# Clock_Sheet.net
KiCad netlist of a schematic drawn in Altium Designer
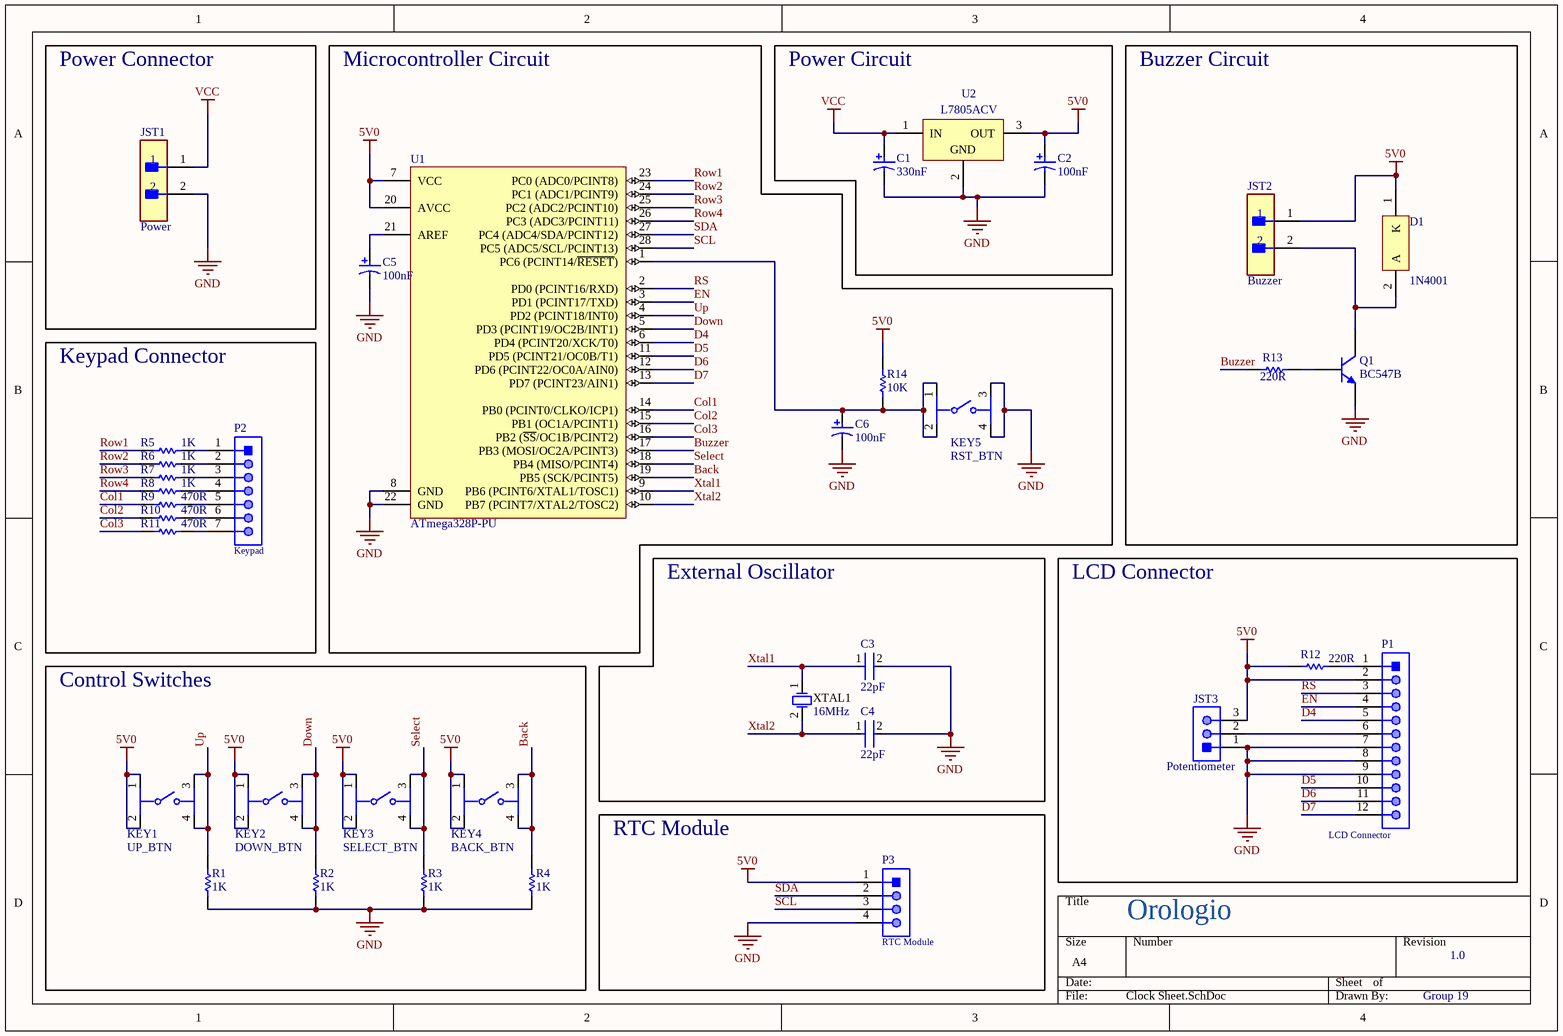
[diagram p0: Clock Sheet.SchDoc]

(export (version "E")
  (design (tool "Eeschema 10.0.6"))
  (components
    (comp (ref "C1")
      (value "330nF")
      (footprint "CAPPR65-350-1150X800X1250")
      (description "Aluminum Electrolytic Capacitor, 100 uF, +/- 20%, 50 V, -40 to 85 degC, 2-Pin THD, RoHS, Bulk")
      (fields (field (name "MANUFACTURER") "Panasonic") (field (name "VOLTAGE") "50V"))
      (libsource (lib "Altium Content Vault") (part "CAP-P-2"))
    )
    (comp (ref "C2")
      (value "100nF")
      (footprint "CAPPR65-350-1150X800X1250")
      (description "Aluminum Electrolytic Capacitor, 100 uF, +/- 20%, 50 V, -40 to 85 degC, 2-Pin THD, RoHS, Bulk")
      (fields (field (name "MANUFACTURER") "Panasonic") (field (name "VOLTAGE") "50V"))
      (libsource (lib "Altium Content Vault") (part "CAP-P-2"))
    )
    (comp (ref "C3")
      (value "22pF")
      (footprint "FP-RCE0K1-MFG")
      (description "Cap Ceramic 22pF 50V C0G ±5% Radial 5mm +125°C Automotive Bulk")
      (fields (field (name "TOLERANCE") "5%"))
      (libsource (lib "Altium Content Vault") (part "b4654b650e69147ec39a6b967a45e02"))
    )
    (comp (ref "C4")
      (value "22pF")
      (footprint "FP-RCE0K1-MFG")
      (description "Cap Ceramic 22pF 50V C0G ±5% Radial 5mm +125°C Automotive Bulk")
      (fields (field (name "TOLERANCE") "5%"))
      (libsource (lib "Altium Content Vault") (part "b4654b650e69147ec39a6b967a45e02"))
    )
    (comp (ref "C5")
      (value "100nF")
      (footprint "CAPPR65-350-1150X800X1250")
      (description "Aluminum Electrolytic Capacitor, 100 uF, +/- 20%, 50 V, -40 to 85 degC, 2-Pin THD, RoHS, Bulk")
      (fields (field (name "MANUFACTURER") "Panasonic") (field (name "VOLTAGE") "50V"))
      (libsource (lib "Altium Content Vault") (part "CAP-P-2"))
    )
    (comp (ref "C6")
      (value "100nF")
      (footprint "CAPPR65-350-1150X800X1250")
      (description "Aluminum Electrolytic Capacitor, 100 uF, +/- 20%, 50 V, -40 to 85 degC, 2-Pin THD, RoHS, Bulk")
      (fields (field (name "MANUFACTURER") "Panasonic") (field (name "VOLTAGE") "50V"))
      (libsource (lib "Altium Content Vault") (part "CAP-P-2"))
    )
    (comp (ref "D1")
      (value "1N4001")
      (footprint "ONSC-AXIAL_LEAD-2-59-10_P")
      (description "Standard Recovery Rectifier, 2-Pin Axial_Lead, Pb-Free, Bulk Bag")
      (fields (field (name "MANUFACTURER") "On Semiconductor"))
      (libsource (lib "Altium Content Vault") (part "ONSC-D-K1A2-2_A"))
    )
    (comp (ref "JST1")
      (value "Power")
      (footprint "FP-440054-2-MFG")
      (description "CONN HEADER VERT 2POS 2MM")
      (fields
        (field (name "MANUFACTURER") "TE Connectivity")
        (field (name "MANUFACTURER PART NUMBER") "440054-2")
      )
      (libsource (lib "Altium Content Vault") (part "3bc925449376181038e59eaffc5286c"))
    )
    (comp (ref "JST2")
      (value "Buzzer")
      (footprint "FP-440054-2-MFG")
      (description "CONN HEADER VERT 2POS 2MM")
      (fields
        (field (name "MANUFACTURER") "TE Connectivity")
        (field (name "MANUFACTURER PART NUMBER") "440054-2")
      )
      (libsource (lib "Altium Content Vault") (part "3bc925449376181038e59eaffc5286c"))
    )
    (comp (ref "JST3")
      (value "Potentiometer")
      (footprint "JST-B3B-PH-K-S-3_V")
      (fields (field (name "MANUFACTURER") "JST"))
      (libsource (lib "Altium Content Vault") (part "CN-1P-M-R3"))
    )
    (comp (ref "KEY1")
      (value "UP_BTN")
      (footprint "FP-1825910-2-0")
      (description "SWITCH TACTILE SPST-NO 0.05A 24V")
      (fields
        (field (name "OCTOPART") "https://octopart.com/1825910-2-te+connectivity-42270502")
        (field (name "MANUFACTURER") "TE")
      )
      (libsource (lib "Altium Content Vault") (part "b8895f3f4cefb76e1819d2863dba89b"))
    )
    (comp (ref "KEY2")
      (value "DOWN_BTN")
      (footprint "FP-1825910-2-0")
      (description "SWITCH TACTILE SPST-NO 0.05A 24V")
      (fields
        (field (name "OCTOPART") "https://octopart.com/1825910-2-te+connectivity-42270502")
        (field (name "MANUFACTURER") "TE")
      )
      (libsource (lib "Altium Content Vault") (part "b8895f3f4cefb76e1819d2863dba89b"))
    )
    (comp (ref "KEY3")
      (value "SELECT_BTN")
      (footprint "FP-1825910-2-0")
      (description "SWITCH TACTILE SPST-NO 0.05A 24V")
      (fields
        (field (name "OCTOPART") "https://octopart.com/1825910-2-te+connectivity-42270502")
        (field (name "MANUFACTURER") "TE")
      )
      (libsource (lib "Altium Content Vault") (part "b8895f3f4cefb76e1819d2863dba89b"))
    )
    (comp (ref "KEY4")
      (value "BACK_BTN")
      (footprint "FP-1825910-2-0")
      (description "SWITCH TACTILE SPST-NO 0.05A 24V")
      (fields
        (field (name "OCTOPART") "https://octopart.com/1825910-2-te+connectivity-42270502")
        (field (name "MANUFACTURER") "TE")
      )
      (libsource (lib "Altium Content Vault") (part "b8895f3f4cefb76e1819d2863dba89b"))
    )
    (comp (ref "KEY5")
      (value "RST_BTN")
      (footprint "FP-1825910-2-0")
      (description "SWITCH TACTILE SPST-NO 0.05A 24V")
      (fields
        (field (name "OCTOPART") "https://octopart.com/1825910-2-te+connectivity-42270502")
        (field (name "MANUFACTURER") "TE")
      )
      (libsource (lib "Altium Content Vault") (part "b8895f3f4cefb76e1819d2863dba89b"))
    )
    (comp (ref "P1")
      (value "LCD Connector")
      (footprint "61301211121")
      (description "THT Vertical Pin Header WR-PHD, Pitch 2.54 mm, Single Row, 12 pins")
      (fields
        (field (name "PART NUMBER") "61301211121")
        (field (name "MANUFACTURER") "Wurth Elektronik")
        (field (name "PUBLISHER") "WurthElektronik")
      )
      (libsource (lib "Altium Content Vault") (part "WE-CN-1P-M-R12"))
    )
    (comp (ref "P2")
      (value "Keypad")
      (footprint "61300711121")
      (description "THT Vertical Pin Header WR-PHD, Pitch 2.54 mm, Single Row, 7 pins")
      (fields
        (field (name "MANUFACTURER") "Wurth Elektronik")
        (field (name "PART NUMBER") "61300711121")
        (field (name "PUBLISHER") "WurthElektronik")
      )
      (libsource (lib "Altium Content Vault") (part "WE-CN-1P-M-R7"))
    )
    (comp (ref "P3")
      (value "RTC Module")
      (footprint "61300411121")
      (description "THT Vertical Pin Header WR-PHD, Pitch 2.54 mm, Single Row, 4 pins")
      (fields
        (field (name "MANUFACTURER") "Wurth Elektronik")
        (field (name "PART NUMBER") "61300411121")
        (field (name "PUBLISHER") "WurthElektronik")
      )
      (libsource (lib "Altium Content Vault") (part "WE-CN-1P-M-R4"))
    )
    (comp (ref "Q1")
      (value "BC547B")
      (footprint "ONSC-TO-92-3-29-11")
      (description "NPN Bipolar Transistor")
      (fields (field (name "PUBLISHER") "Altium Limited"))
      (libsource (lib "Miscellaneous Devices") (part "NPN"))
    )
    (comp (ref "R1")
      (value "1K")
      (footprint "AXIAL-0.3")
      (description "Resistor")
      (fields (field (name "PUBLISHER") "Altium Limited"))
      (libsource (lib "Miscellaneous Devices") (part "Res1"))
    )
    (comp (ref "R2")
      (value "1K")
      (footprint "AXIAL-0.3")
      (description "Resistor")
      (fields (field (name "PUBLISHER") "Altium Limited"))
      (libsource (lib "Miscellaneous Devices") (part "Res1"))
    )
    (comp (ref "R3")
      (value "1K")
      (footprint "AXIAL-0.3")
      (description "Resistor")
      (fields (field (name "PUBLISHER") "Altium Limited"))
      (libsource (lib "Miscellaneous Devices") (part "Res1"))
    )
    (comp (ref "R4")
      (value "1K")
      (footprint "AXIAL-0.3")
      (description "Resistor")
      (fields (field (name "PUBLISHER") "Altium Limited"))
      (libsource (lib "Miscellaneous Devices") (part "Res1"))
    )
    (comp (ref "R5")
      (value "1K")
      (footprint "AXIAL-0.3")
      (description "Resistor")
      (fields (field (name "PUBLISHER") "Altium Limited"))
      (libsource (lib "Miscellaneous Devices") (part "Res1"))
    )
    (comp (ref "R6")
      (value "1K")
      (footprint "AXIAL-0.3")
      (description "Resistor")
      (fields (field (name "PUBLISHER") "Altium Limited"))
      (libsource (lib "Miscellaneous Devices") (part "Res1"))
    )
    (comp (ref "R7")
      (value "1K")
      (footprint "AXIAL-0.3")
      (description "Resistor")
      (fields (field (name "PUBLISHER") "Altium Limited"))
      (libsource (lib "Miscellaneous Devices") (part "Res1"))
    )
    (comp (ref "R8")
      (value "1K")
      (footprint "AXIAL-0.3")
      (description "Resistor")
      (fields (field (name "PUBLISHER") "Altium Limited"))
      (libsource (lib "Miscellaneous Devices") (part "Res1"))
    )
    (comp (ref "R9")
      (value "470R")
      (footprint "AXIAL-0.3")
      (description "Resistor")
      (fields (field (name "PUBLISHER") "Altium Limited"))
      (libsource (lib "Miscellaneous Devices") (part "Res1"))
    )
    (comp (ref "R10")
      (value "470R")
      (footprint "AXIAL-0.3")
      (description "Resistor")
      (fields (field (name "PUBLISHER") "Altium Limited"))
      (libsource (lib "Miscellaneous Devices") (part "Res1"))
    )
    (comp (ref "R11")
      (value "470R")
      (footprint "AXIAL-0.3")
      (description "Resistor")
      (fields (field (name "PUBLISHER") "Altium Limited"))
      (libsource (lib "Miscellaneous Devices") (part "Res1"))
    )
    (comp (ref "R12")
      (value "220R")
      (footprint "AXIAL-0.3")
      (description "Resistor")
      (fields (field (name "PUBLISHER") "Altium Limited"))
      (libsource (lib "Miscellaneous Devices") (part "Res1"))
    )
    (comp (ref "R13")
      (value "220R")
      (footprint "AXIAL-0.3")
      (description "Resistor")
      (fields (field (name "PUBLISHER") "Altium Limited"))
      (libsource (lib "Miscellaneous Devices") (part "Res1"))
    )
    (comp (ref "R14")
      (value "10K")
      (footprint "AXIAL-0.3")
      (description "Resistor")
      (fields (field (name "PUBLISHER") "Altium Limited"))
      (libsource (lib "Miscellaneous Devices") (part "Res1"))
    )
    (comp (ref "U1")
      (value "ATmega328P-PU")
      (footprint "28P3")
      (libsource (lib "Altium Content Vault") (part "MC-8B-ATM48-IL28"))
    )
    (comp (ref "U2")
      (value "L7805ACV")
      (footprint "TO220")
      (description "Positive Voltage Regulator, 5V, 3-Pin TO-220")
      (libsource (lib "Altium Content Vault") (part "PM-REG-L4940-SIL3"))
    )
    (comp (ref "XTAL1")
      (value "16MHz")
      (footprint "FOX-FOXSLF160-20")
      (description "Resistance Weld Thru-Hole Crystal, 16 MHz, -20 to 70 degC, 2-Pin THD, RoHS, Bulk")
      (fields (field (name "TOLERANCE") "1%"))
      (libsource (lib "Altium Content Vault") (part "XTAL-1-2-2"))
    )
  )
  (nets
    (net (code "1") (name "/Back") (class "Default")
      (node (ref "KEY4") (pin "3") (pinfunction "3_3") (pintype "passive"))
      (node (ref "KEY4") (pin "4") (pinfunction "4_4") (pintype "passive"))
      (node (ref "R4") (pin "2") (pinfunction "2_2") (pintype "passive"))
      (node (ref "U1") (pin "19") (pinfunction "PB5_(SCK/PCINT5)_19") (pintype "bidirectional"))
    )
    (net (code "2") (name "/Buzzer") (class "Default")
      (node (ref "R13") (pin "1") (pinfunction "1_1") (pintype "passive"))
      (node (ref "U1") (pin "17") (pinfunction "PB3_(MOSI/OC2A/PCINT3)_17") (pintype "bidirectional"))
    )
    (net (code "3") (name "/Col1") (class "Default")
      (node (ref "R9") (pin "2") (pinfunction "2_2") (pintype "passive"))
      (node (ref "U1") (pin "14") (pinfunction "PB0_(PCINT0/CLKO/ICP1)_14") (pintype "bidirectional"))
    )
    (net (code "4") (name "/Col2") (class "Default")
      (node (ref "R10") (pin "2") (pinfunction "2_2") (pintype "passive"))
      (node (ref "U1") (pin "15") (pinfunction "PB1_(OC1A/PCINT1)_15") (pintype "bidirectional"))
    )
    (net (code "5") (name "/Col3") (class "Default")
      (node (ref "R11") (pin "2") (pinfunction "2_2") (pintype "passive"))
      (node (ref "U1") (pin "16") (pinfunction "PB2_(~{SS}/OC1B/PCINT2)_16") (pintype "bidirectional"))
    )
    (net (code "6") (name "/D4") (class "Default")
      (node (ref "P1") (pin "5") (pinfunction "5_5") (pintype "passive"))
      (node (ref "U1") (pin "6") (pinfunction "PD4_(PCINT20/XCK/T0)_6") (pintype "bidirectional"))
    )
    (net (code "7") (name "/D5") (class "Default")
      (node (ref "P1") (pin "10") (pinfunction "10_10") (pintype "passive"))
      (node (ref "U1") (pin "11") (pinfunction "PD5_(PCINT21/OC0B/T1)_11") (pintype "bidirectional"))
    )
    (net (code "8") (name "/D6") (class "Default")
      (node (ref "P1") (pin "11") (pinfunction "11_11") (pintype "passive"))
      (node (ref "U1") (pin "12") (pinfunction "PD6_(PCINT22/OC0A/AIN0)_12") (pintype "bidirectional"))
    )
    (net (code "9") (name "/D7") (class "Default")
      (node (ref "P1") (pin "12") (pinfunction "12_12") (pintype "passive"))
      (node (ref "U1") (pin "13") (pinfunction "PD7_(PCINT23/AIN1)_13") (pintype "bidirectional"))
    )
    (net (code "10") (name "/Down") (class "Default")
      (node (ref "KEY2") (pin "3") (pinfunction "3_3") (pintype "passive"))
      (node (ref "KEY2") (pin "4") (pinfunction "4_4") (pintype "passive"))
      (node (ref "R2") (pin "1") (pinfunction "1_1") (pintype "passive"))
      (node (ref "U1") (pin "5") (pinfunction "PD3_(PCINT19/OC2B/INT1)_5") (pintype "bidirectional"))
    )
    (net (code "11") (name "/EN") (class "Default")
      (node (ref "P1") (pin "4") (pinfunction "4_4") (pintype "passive"))
      (node (ref "U1") (pin "3") (pinfunction "PD1_(PCINT17/TXD)_3") (pintype "bidirectional"))
    )
    (net (code "12") (name "/RS") (class "Default")
      (node (ref "P1") (pin "3") (pinfunction "3_3") (pintype "passive"))
      (node (ref "U1") (pin "2") (pinfunction "PD0_(PCINT16/RXD)_2") (pintype "bidirectional"))
    )
    (net (code "13") (name "/Row1") (class "Default")
      (node (ref "R5") (pin "2") (pinfunction "2_2") (pintype "passive"))
      (node (ref "U1") (pin "23") (pinfunction "PC0_(ADC0/PCINT8)_23") (pintype "bidirectional"))
    )
    (net (code "14") (name "/Row2") (class "Default")
      (node (ref "R6") (pin "2") (pinfunction "2_2") (pintype "passive"))
      (node (ref "U1") (pin "24") (pinfunction "PC1_(ADC1/PCINT9)_24") (pintype "bidirectional"))
    )
    (net (code "15") (name "/Row3") (class "Default")
      (node (ref "R7") (pin "2") (pinfunction "2_2") (pintype "passive"))
      (node (ref "U1") (pin "25") (pinfunction "PC2_(ADC2/PCINT10)_25") (pintype "bidirectional"))
    )
    (net (code "16") (name "/Row4") (class "Default")
      (node (ref "R8") (pin "2") (pinfunction "2_2") (pintype "passive"))
      (node (ref "U1") (pin "26") (pinfunction "PC3_(ADC3/PCINT11)_26") (pintype "bidirectional"))
    )
    (net (code "17") (name "/SCL") (class "Default")
      (node (ref "P3") (pin "3") (pinfunction "3_3") (pintype "passive"))
      (node (ref "U1") (pin "28") (pinfunction "PC5_(ADC5/SCL/PCINT13)_28") (pintype "bidirectional"))
    )
    (net (code "18") (name "/SDA") (class "Default")
      (node (ref "P3") (pin "2") (pinfunction "2_2") (pintype "passive"))
      (node (ref "U1") (pin "27") (pinfunction "PC4_(ADC4/SDA/PCINT12)_27") (pintype "bidirectional"))
    )
    (net (code "19") (name "/Select") (class "Default")
      (node (ref "KEY3") (pin "3") (pinfunction "3_3") (pintype "passive"))
      (node (ref "KEY3") (pin "4") (pinfunction "4_4") (pintype "passive"))
      (node (ref "R3") (pin "2") (pinfunction "2_2") (pintype "passive"))
      (node (ref "U1") (pin "18") (pinfunction "PB4_(MISO/PCINT4)_18") (pintype "bidirectional"))
    )
    (net (code "20") (name "/Up") (class "Default")
      (node (ref "KEY1") (pin "3") (pinfunction "3_3") (pintype "passive"))
      (node (ref "KEY1") (pin "4") (pinfunction "4_4") (pintype "passive"))
      (node (ref "R1") (pin "1") (pinfunction "1_1") (pintype "passive"))
      (node (ref "U1") (pin "4") (pinfunction "PD2_(PCINT18/INT0)_4") (pintype "bidirectional"))
    )
    (net (code "21") (name "/Xtal1") (class "Default")
      (node (ref "C3") (pin "1") (pinfunction "1_1") (pintype "passive"))
      (node (ref "U1") (pin "9") (pinfunction "PB6_(PCINT6/XTAL1/TOSC1)_9") (pintype "bidirectional"))
      (node (ref "XTAL1") (pin "1") (pinfunction "1_1") (pintype "passive"))
    )
    (net (code "22") (name "/Xtal2") (class "Default")
      (node (ref "C4") (pin "1") (pinfunction "1_1") (pintype "passive"))
      (node (ref "U1") (pin "10") (pinfunction "PB7_(PCINT7/XTAL2/TOSC2)_10") (pintype "bidirectional"))
      (node (ref "XTAL1") (pin "2") (pinfunction "2_2") (pintype "passive"))
    )
    (net (code "23") (name "5V0") (class "Default")
      (node (ref "C2") (pin "1") (pinfunction "1_1") (pintype "passive"))
      (node (ref "D1") (pin "1") (pinfunction "K_1") (pintype "passive"))
      (node (ref "JST2") (pin "1") (pinfunction "1_1") (pintype "passive"))
      (node (ref "JST3") (pin "3") (pinfunction "3_3") (pintype "passive"))
      (node (ref "KEY1") (pin "1") (pinfunction "1_1") (pintype "passive"))
      (node (ref "KEY1") (pin "2") (pinfunction "2_2") (pintype "passive"))
      (node (ref "KEY2") (pin "1") (pinfunction "1_1") (pintype "passive"))
      (node (ref "KEY2") (pin "2") (pinfunction "2_2") (pintype "passive"))
      (node (ref "KEY3") (pin "1") (pinfunction "1_1") (pintype "passive"))
      (node (ref "KEY3") (pin "2") (pinfunction "2_2") (pintype "passive"))
      (node (ref "KEY4") (pin "1") (pinfunction "1_1") (pintype "passive"))
      (node (ref "KEY4") (pin "2") (pinfunction "2_2") (pintype "passive"))
      (node (ref "P1") (pin "2") (pinfunction "2_2") (pintype "passive"))
      (node (ref "P3") (pin "1") (pinfunction "1_1") (pintype "passive"))
      (node (ref "R12") (pin "1") (pinfunction "1_1") (pintype "passive"))
      (node (ref "R14") (pin "2") (pinfunction "2_2") (pintype "passive"))
      (node (ref "U1") (pin "20") (pinfunction "AVCC_20") (pintype "power_in"))
      (node (ref "U1") (pin "7") (pinfunction "VCC_7") (pintype "power_in"))
      (node (ref "U2") (pin "3") (pinfunction "OUT_3") (pintype "power_in"))
    )
    (net (code "24") (name "GND") (class "Default")
      (node (ref "C1") (pin "2") (pinfunction "2_2") (pintype "passive"))
      (node (ref "C2") (pin "2") (pinfunction "2_2") (pintype "passive"))
      (node (ref "C3") (pin "2") (pinfunction "2_2") (pintype "passive"))
      (node (ref "C4") (pin "2") (pinfunction "2_2") (pintype "passive"))
      (node (ref "C5") (pin "2") (pinfunction "2_2") (pintype "passive"))
      (node (ref "C6") (pin "2") (pinfunction "2_2") (pintype "passive"))
      (node (ref "JST1") (pin "2") (pinfunction "2_2") (pintype "passive"))
      (node (ref "JST3") (pin "1") (pinfunction "1_1") (pintype "passive"))
      (node (ref "KEY5") (pin "3") (pinfunction "3_3") (pintype "passive"))
      (node (ref "KEY5") (pin "4") (pinfunction "4_4") (pintype "passive"))
      (node (ref "P1") (pin "7") (pinfunction "7_7") (pintype "passive"))
      (node (ref "P1") (pin "8") (pinfunction "8_8") (pintype "passive"))
      (node (ref "P1") (pin "9") (pinfunction "9_9") (pintype "passive"))
      (node (ref "P3") (pin "4") (pinfunction "4_4") (pintype "passive"))
      (node (ref "Q1") (pin "3") (pinfunction "E_3") (pintype "passive"))
      (node (ref "R1") (pin "2") (pinfunction "2_2") (pintype "passive"))
      (node (ref "R2") (pin "2") (pinfunction "2_2") (pintype "passive"))
      (node (ref "R3") (pin "1") (pinfunction "1_1") (pintype "passive"))
      (node (ref "R4") (pin "1") (pinfunction "1_1") (pintype "passive"))
      (node (ref "U1") (pin "22") (pinfunction "GND_22") (pintype "power_in"))
      (node (ref "U1") (pin "8") (pinfunction "GND_8") (pintype "power_in"))
      (node (ref "U2") (pin "2") (pinfunction "GND_2") (pintype "power_in"))
    )
    (net (code "25") (name "Net-(D1-A)") (class "Default")
      (node (ref "D1") (pin "2") (pinfunction "A_2") (pintype "passive"))
      (node (ref "JST2") (pin "2") (pinfunction "2_2") (pintype "passive"))
    )
    (net (code "26") (name "Net-(JST3-Pad2)") (class "Default")
      (node (ref "JST3") (pin "2") (pinfunction "2_2") (pintype "passive"))
      (node (ref "P1") (pin "6") (pinfunction "6_6") (pintype "passive"))
    )
    (net (code "27") (name "Net-(P1-Pad1)") (class "Default")
      (node (ref "P1") (pin "1") (pinfunction "1_1") (pintype "passive"))
      (node (ref "R12") (pin "2") (pinfunction "2_2") (pintype "passive"))
    )
    (net (code "28") (name "Net-(P2-Pad1)") (class "Default")
      (node (ref "P2") (pin "1") (pinfunction "1_1") (pintype "passive"))
      (node (ref "R5") (pin "1") (pinfunction "1_1") (pintype "passive"))
    )
    (net (code "29") (name "Net-(P2-Pad2)") (class "Default")
      (node (ref "P2") (pin "2") (pinfunction "2_2") (pintype "passive"))
      (node (ref "R6") (pin "1") (pinfunction "1_1") (pintype "passive"))
    )
    (net (code "30") (name "Net-(P2-Pad3)") (class "Default")
      (node (ref "P2") (pin "3") (pinfunction "3_3") (pintype "passive"))
      (node (ref "R7") (pin "1") (pinfunction "1_1") (pintype "passive"))
    )
    (net (code "31") (name "Net-(P2-Pad4)") (class "Default")
      (node (ref "P2") (pin "4") (pinfunction "4_4") (pintype "passive"))
      (node (ref "R8") (pin "1") (pinfunction "1_1") (pintype "passive"))
    )
    (net (code "32") (name "Net-(P2-Pad5)") (class "Default")
      (node (ref "P2") (pin "5") (pinfunction "5_5") (pintype "passive"))
      (node (ref "R9") (pin "1") (pinfunction "1_1") (pintype "passive"))
    )
    (net (code "33") (name "Net-(P2-Pad6)") (class "Default")
      (node (ref "P2") (pin "6") (pinfunction "6_6") (pintype "passive"))
      (node (ref "R10") (pin "1") (pinfunction "1_1") (pintype "passive"))
    )
    (net (code "34") (name "Net-(P2-Pad7)") (class "Default")
      (node (ref "P2") (pin "7") (pinfunction "7_7") (pintype "passive"))
      (node (ref "R11") (pin "1") (pinfunction "1_1") (pintype "passive"))
    )
    (net (code "35") (name "Net-(Q1-B)") (class "Default")
      (node (ref "Q1") (pin "2") (pinfunction "B_2") (pintype "passive"))
      (node (ref "R13") (pin "2") (pinfunction "2_2") (pintype "passive"))
    )
    (net (code "36") (name "Net-(U1-AREF)") (class "Default")
      (node (ref "C5") (pin "1") (pinfunction "1_1") (pintype "passive"))
      (node (ref "U1") (pin "21") (pinfunction "AREF_21") (pintype "power_in"))
    )
    (net (code "37") (name "Net-(U1-PC6_(PCINT14{slash}~{RESET}))") (class "Default")
      (node (ref "C6") (pin "1") (pinfunction "1_1") (pintype "passive"))
      (node (ref "KEY5") (pin "1") (pinfunction "1_1") (pintype "passive"))
      (node (ref "KEY5") (pin "2") (pinfunction "2_2") (pintype "passive"))
      (node (ref "R14") (pin "1") (pinfunction "1_1") (pintype "passive"))
      (node (ref "U1") (pin "1") (pinfunction "PC6_(PCINT14/~{RESET})_1") (pintype "bidirectional"))
    )
    (net (code "38") (name "VCC") (class "Default")
      (node (ref "C1") (pin "1") (pinfunction "1_1") (pintype "passive"))
      (node (ref "JST1") (pin "1") (pinfunction "1_1") (pintype "passive"))
      (node (ref "U2") (pin "1") (pinfunction "IN_1") (pintype "power_in"))
    )
    (net (code "39") (name "unconnected-(Q1-C-Pad1)") (class "Default")
      (node (ref "Q1") (pin "1") (pinfunction "C_1") (pintype "passive"))
    )
  )
)
